# board2.net
KiCad netlist of a schematic drawn in Altium Designer
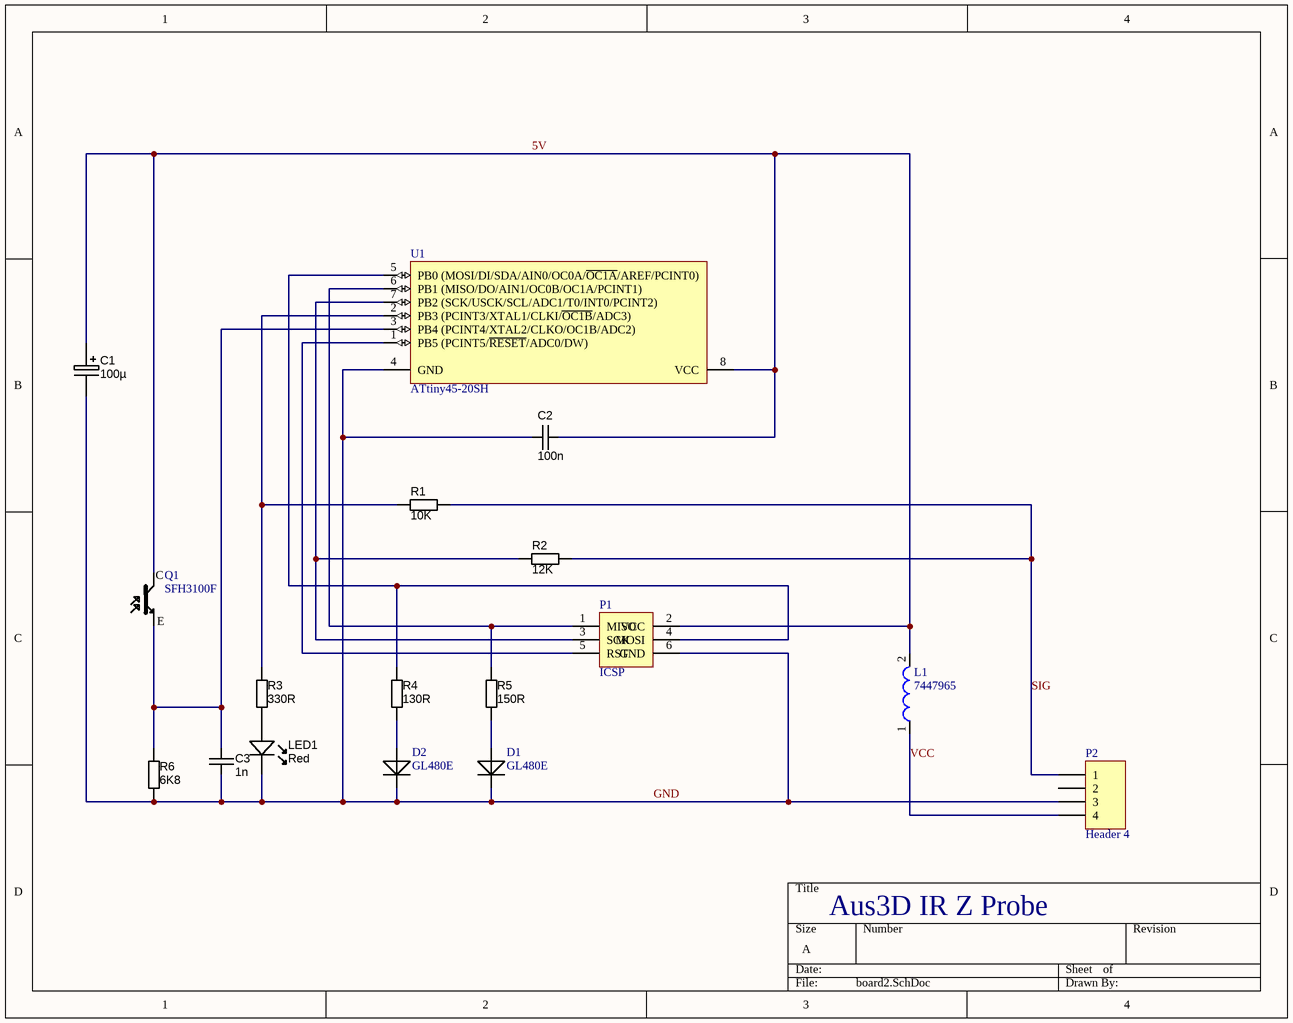
[diagram p0: board2.SchDoc]

(export (version "E")
  (design (tool "Eeschema 10.0.6"))
  (components
    (comp (ref "C1")
      (value "100µ")
      (footprint "6.3-DIA-CAP")
      (description "Capacitor THD Electrolytic 100uF 20% 16V Radial")
      (fields (field (name "TOLERANCE") "±20%") (field (name "MANUFACTURER") "Panasonic - ECG"))
      (libsource (lib "PBL - Capacitors") (part "CAPE_100u_16V_THD"))
    )
    (comp (ref "C2")
      (value "100n")
      (footprint "CAPC1005X55N")
      (description "Capacitor SMD Cer 100nF 10% 16V X5R 0402")
      (fields (field (name "TOLERANCE") "±10%"))
      (libsource (lib "PBL - Capacitors") (part "CAPC_100n_0402_X5R_16V_10%"))
    )
    (comp (ref "C3")
      (value "1n")
      (footprint "CAPC1005X55N")
      (description "Capacitor SMD Cer 1nF 10% 16V X7R 0402")
      (fields (field (name "TOLERANCE") "±10%"))
      (libsource (lib "PBL - Capacitors") (part "CAPC_1n_0402_X7R_16V_10%"))
    )
    (comp (ref "D1")
      (value "GL480E")
      (footprint "LED-2.54spacing")
      (libsource (lib "Schlib1") (part "GL480E"))
    )
    (comp (ref "D2")
      (value "GL480E")
      (footprint "LED-2.54spacing")
      (libsource (lib "Schlib1") (part "GL480E"))
    )
    (comp (ref "L1")
      (value "7447965")
      (footprint "SMD-0603")
      (description "SMD-Multilayer Inductor WE-MI, L = 1.00 µH")
      (libsource (lib "Wuerth Elektronik Filter Inductor") (part "7447965"))
    )
    (comp (ref "LED1")
      (value "Red")
      (footprint "LED-0603-RED")
      (description "LED 0603 SMD Hyper Red 630nm 220mcd 20mA")
      (libsource (lib "PBL - Light Sources") (part "LED_SMD_Red_0603_220mcd"))
    )
    (comp (ref "P1")
      (value "ICSP")
      (footprint "ICSP Pads - SMD")
      (description "Header, 3-Pin, Dual row")
      (fields (field (name "PUBLISHER") "Altium Limited"))
      (libsource (lib "Miscellaneous Connectors") (part "Header 3X2"))
    )
    (comp (ref "P2")
      (value "Header 4")
      (footprint "JST-4P")
      (description "Header, 4-Pin")
      (fields (field (name "PUBLISHER") "Altium Limited"))
      (libsource (lib "Miscellaneous Connectors") (part "Header 4"))
    )
    (comp (ref "Q1")
      (value "SFH3100F")
      (footprint "SFH3100F-footprint")
      (description "GL480E")
      (libsource (lib "Schlib1") (part "SFH3100F"))
    )
    (comp (ref "R1")
      (value "10K")
      (footprint "RESC1608X55N")
      (description "Resistor SMD chip 2.2k Ohm 0.1W 5% 0603")
      (fields (field (name "TOLERANCE") "±5%") (field (name "Comment") "Thick Film"))
      (libsource (lib "PBL - Resistors") (part "RES_2K2_0603_5%"))
    )
    (comp (ref "R2")
      (value "12K")
      (footprint "RESC1608X55N")
      (description "Resistor SMD chip 2.2k Ohm 0.1W 5% 0603")
      (fields (field (name "TOLERANCE") "±5%") (field (name "Comment") "Thick Film"))
      (libsource (lib "PBL - Resistors") (part "RES_2K2_0603_5%"))
    )
    (comp (ref "R3")
      (value "330R")
      (footprint "RESC1608X55N")
      (description "Resistor SMD chip 330 Ohm 0.1W 5% 0603")
      (fields (field (name "TOLERANCE") "±5%") (field (name "Comment") "Thick Film"))
      (libsource (lib "PBL - Resistors") (part "RES_330R_0603_5%"))
    )
    (comp (ref "R4")
      (value "130R")
      (footprint "RESC1608X55N")
      (description "Resistor SMD chip 2.2k Ohm 0.1W 5% 0603")
      (fields (field (name "TOLERANCE") "±5%") (field (name "Comment") "Thick Film"))
      (libsource (lib "") (part "RES_2K2_0603_5%_1"))
    )
    (comp (ref "R5")
      (value "150R")
      (footprint "RESC1608X55N")
      (description "Resistor SMD chip 2.2k Ohm 0.1W 5% 0603")
      (fields (field (name "TOLERANCE") "±5%") (field (name "Comment") "Thick Film"))
      (libsource (lib "") (part "RES_2K2_0603_5%_1"))
    )
    (comp (ref "R6")
      (value "6K8")
      (footprint "RESC1608X55N")
      (description "Resistor SMD chip 2.2k Ohm 0.1W 5% 0603")
      (fields (field (name "TOLERANCE") "±5%") (field (name "Comment") "Thick Film"))
      (libsource (lib "") (part "RES_2K2_0603_5%_1"))
    )
    (comp (ref "U1")
      (value "ATtiny45-20SH")
      (footprint "8S2_N")
      (libsource (lib "Atmel Microcontroller tinyAVR") (part "ATtiny45-20SH"))
    )
  )
  (nets
    (net (code "1") (name "/5V") (class "Default")
      (node (ref "C1") (pin "1") (pintype "passive"))
      (node (ref "C2") (pin "2") (pintype "passive"))
      (node (ref "L1") (pin "2") (pinfunction "2_2") (pintype "passive"))
      (node (ref "P1") (pin "2") (pinfunction "VCC_2") (pintype "passive"))
      (node (ref "Q1") (pin "1") (pinfunction "1_1") (pintype "passive"))
      (node (ref "U1") (pin "8") (pinfunction "VCC_8") (pintype "power_in"))
    )
    (net (code "2") (name "/GND") (class "Default")
      (node (ref "C1") (pin "2") (pintype "passive"))
      (node (ref "C2") (pin "1") (pintype "passive"))
      (node (ref "C3") (pin "2") (pintype "passive"))
      (node (ref "D1") (pin "1") (pinfunction "1_1") (pintype "passive"))
      (node (ref "D2") (pin "1") (pinfunction "1_1") (pintype "passive"))
      (node (ref "LED1") (pin "K") (pinfunction "K_K") (pintype "passive"))
      (node (ref "P1") (pin "6") (pinfunction "GND_6") (pintype "passive"))
      (node (ref "P2") (pin "3") (pinfunction "3_3") (pintype "passive"))
      (node (ref "R6") (pin "1") (pinfunction "1_1") (pintype "passive"))
      (node (ref "U1") (pin "4") (pinfunction "GND_4") (pintype "power_in"))
    )
    (net (code "3") (name "/SIG") (class "Default")
      (node (ref "P2") (pin "1") (pinfunction "1_1") (pintype "passive"))
      (node (ref "R1") (pin "1") (pinfunction "1_1") (pintype "passive"))
      (node (ref "R2") (pin "1") (pinfunction "1_1") (pintype "passive"))
    )
    (net (code "4") (name "/VCC") (class "Default")
      (node (ref "L1") (pin "1") (pinfunction "1_1") (pintype "passive"))
      (node (ref "P2") (pin "4") (pinfunction "4_4") (pintype "passive"))
    )
    (net (code "5") (name "Net-(D1-Pad2)") (class "Default")
      (node (ref "D1") (pin "2") (pinfunction "2_2") (pintype "passive"))
      (node (ref "R5") (pin "1") (pinfunction "1_1") (pintype "passive"))
    )
    (net (code "6") (name "Net-(D2-Pad2)") (class "Default")
      (node (ref "D2") (pin "2") (pinfunction "2_2") (pintype "passive"))
      (node (ref "R4") (pin "1") (pinfunction "1_1") (pintype "passive"))
    )
    (net (code "7") (name "Net-(LED1-PadA)") (class "Default")
      (node (ref "LED1") (pin "A") (pinfunction "A_A") (pintype "passive"))
      (node (ref "R3") (pin "2") (pinfunction "2_2") (pintype "passive"))
    )
    (net (code "8") (name "Net-(P1-MISO)") (class "Default")
      (node (ref "P1") (pin "1") (pinfunction "MISO_1") (pintype "passive"))
      (node (ref "R5") (pin "2") (pinfunction "2_2") (pintype "passive"))
      (node (ref "U1") (pin "6") (pinfunction "PB1_(MISO/DO/AIN1/OC0B/OC1A/PCINT1)_6") (pintype "bidirectional"))
    )
    (net (code "9") (name "Net-(P1-MOSI)") (class "Default")
      (node (ref "P1") (pin "4") (pinfunction "MOSI_4") (pintype "passive"))
      (node (ref "R4") (pin "2") (pinfunction "2_2") (pintype "passive"))
      (node (ref "U1") (pin "5") (pinfunction "PB0_(MOSI/DI/SDA/AIN0/OC0A/~{OC1A}/AREF/PCINT0)_5") (pintype "bidirectional"))
    )
    (net (code "10") (name "Net-(P1-RST)") (class "Default")
      (node (ref "P1") (pin "5") (pinfunction "RST_5") (pintype "passive"))
      (node (ref "U1") (pin "1") (pinfunction "PB5_(PCINT5/~{RESET}/ADC0/DW)_1") (pintype "bidirectional"))
    )
    (net (code "11") (name "Net-(P1-SCK)") (class "Default")
      (node (ref "P1") (pin "3") (pinfunction "SCK_3") (pintype "passive"))
      (node (ref "R2") (pin "2") (pinfunction "2_2") (pintype "passive"))
      (node (ref "U1") (pin "7") (pinfunction "PB2_(SCK/USCK/SCL/ADC1/T0/INT0/PCINT2)_7") (pintype "bidirectional"))
    )
    (net (code "12") (name "Net-(U1-PB3_(PCINT3{slash}XTAL1{slash}CLKI{slash}~{OC1B}{slash}ADC3))") (class "Default")
      (node (ref "R1") (pin "2") (pinfunction "2_2") (pintype "passive"))
      (node (ref "R3") (pin "1") (pinfunction "1_1") (pintype "passive"))
      (node (ref "U1") (pin "2") (pinfunction "PB3_(PCINT3/XTAL1/CLKI/~{OC1B}/ADC3)_2") (pintype "bidirectional"))
    )
    (net (code "13") (name "Net-(U1-PB4_(PCINT4{slash}XTAL2{slash}CLKO{slash}OC1B{slash}ADC2))") (class "Default")
      (node (ref "C3") (pin "1") (pintype "passive"))
      (node (ref "Q1") (pin "2") (pinfunction "2_2") (pintype "passive"))
      (node (ref "R6") (pin "2") (pinfunction "2_2") (pintype "passive"))
      (node (ref "U1") (pin "3") (pinfunction "PB4_(PCINT4/XTAL2/CLKO/OC1B/ADC2)_3") (pintype "bidirectional"))
    )
    (net (code "14") (name "unconnected-(P2-Pad2)") (class "Default")
      (node (ref "P2") (pin "2") (pinfunction "2_2") (pintype "passive"))
    )
  )
)
